# music_box.net
KiCad netlist of a schematic drawn in EAGLE
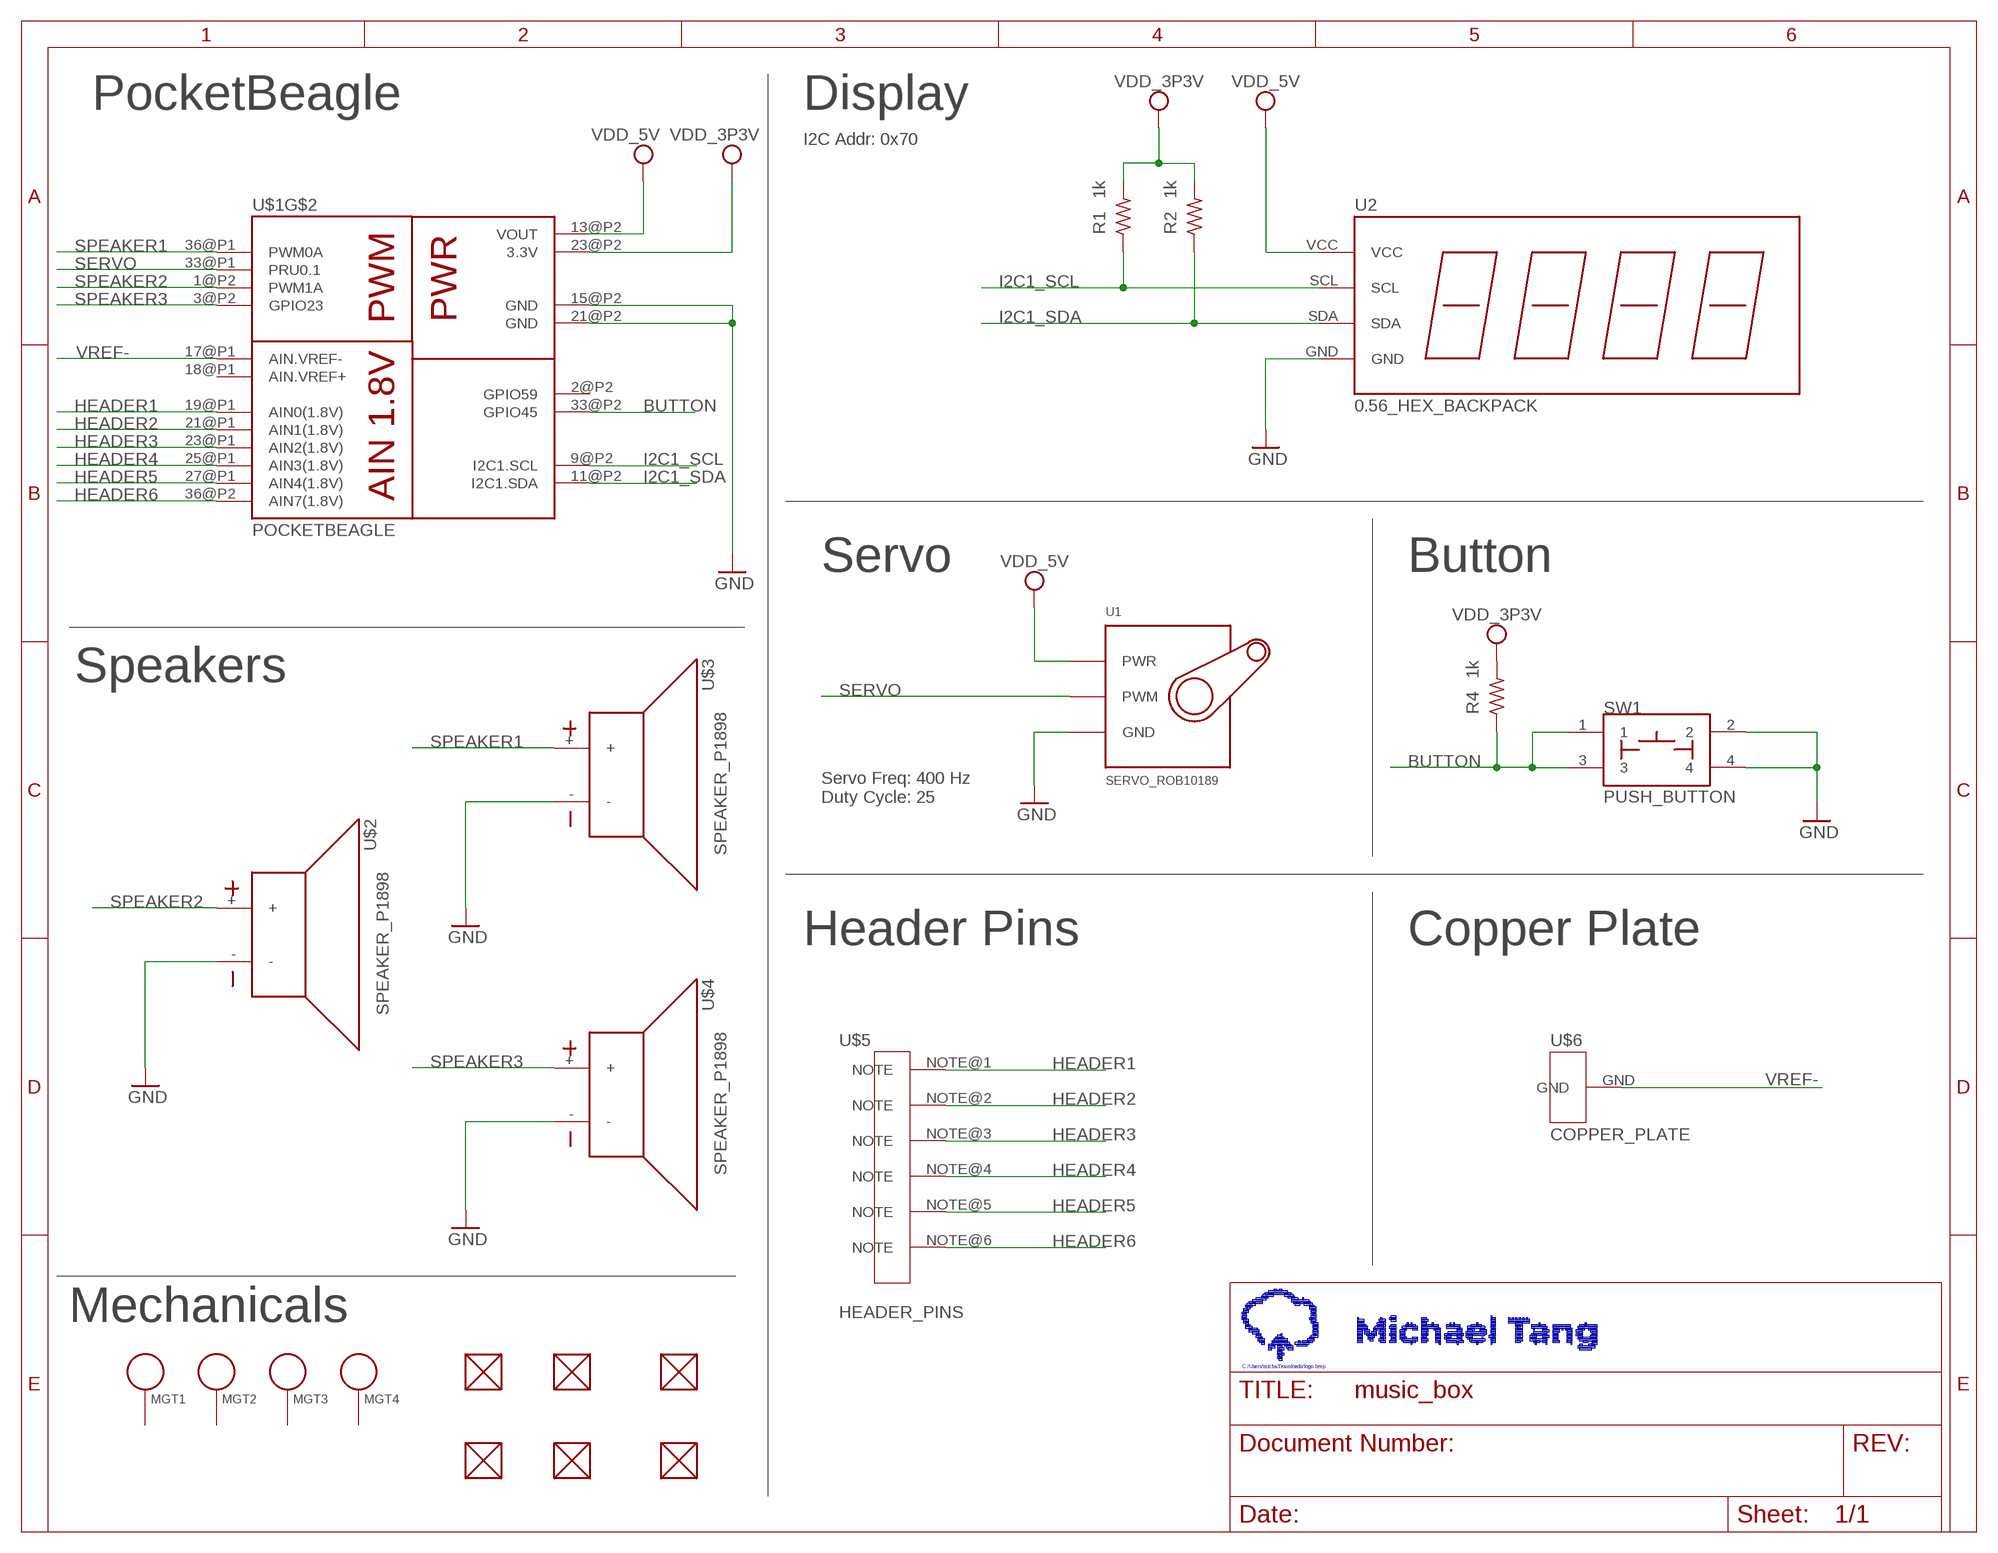
[diagram p0: schematic, sheet 1]

(export (version "E")
  (design (tool "Eeschema 10.0.6"))
  (components
    (comp (ref "FUD1")
      (value "FIDUCIAL")
      (footprint "eagle-import:FIDUCIAL_40MIL")
      (libsource (lib "eagle-import") (part "FIDUCIAL"))
    )
    (comp (ref "FUD2")
      (value "FIDUCIAL")
      (footprint "eagle-import:FIDUCIAL_40MIL")
      (libsource (lib "eagle-import") (part "FIDUCIAL"))
    )
    (comp (ref "FUD3")
      (value "FIDUCIAL")
      (footprint "eagle-import:FIDUCIAL_40MIL")
      (libsource (lib "eagle-import") (part "FIDUCIAL"))
    )
    (comp (ref "FUD4")
      (value "FIDUCIAL")
      (footprint "eagle-import:FIDUCIAL_40MIL")
      (libsource (lib "eagle-import") (part "FIDUCIAL"))
    )
    (comp (ref "FUD5")
      (value "FIDUCIAL")
      (footprint "eagle-import:FIDUCIAL_40MIL")
      (libsource (lib "eagle-import") (part "FIDUCIAL"))
    )
    (comp (ref "FUD6")
      (value "FIDUCIAL")
      (footprint "eagle-import:FIDUCIAL_40MIL")
      (libsource (lib "eagle-import") (part "FIDUCIAL"))
    )
    (comp (ref "MGT1")
      (value "MOUNTING_HOLE")
      (footprint "eagle-import:MOUNTING_HOLE")
      (libsource (lib "eagle-import") (part "MOUNTING_HOLE"))
    )
    (comp (ref "MGT2")
      (value "MOUNTING_HOLE")
      (footprint "eagle-import:MOUNTING_HOLE")
      (libsource (lib "eagle-import") (part "MOUNTING_HOLE"))
    )
    (comp (ref "MGT3")
      (value "MOUNTING_HOLE")
      (footprint "eagle-import:MOUNTING_HOLE")
      (libsource (lib "eagle-import") (part "MOUNTING_HOLE"))
    )
    (comp (ref "MGT4")
      (value "MOUNTING_HOLE")
      (footprint "eagle-import:MOUNTING_HOLE")
      (libsource (lib "eagle-import") (part "MOUNTING_HOLE"))
    )
    (comp (ref "R1")
      (value "1k")
      (footprint "eagle-import:R0603")
      (libsource (lib "eagle-import") (part "R_R0603"))
    )
    (comp (ref "R2")
      (value "1k")
      (footprint "eagle-import:R0603")
      (libsource (lib "eagle-import") (part "R_R0603"))
    )
    (comp (ref "R4")
      (value "1k")
      (footprint "eagle-import:R0603")
      (libsource (lib "eagle-import") (part "R_R0603"))
    )
    (comp (ref "SW1")
      (value "PUSH_BUTTON")
      (footprint "eagle-import:BUTTON_12.5MM")
      (libsource (lib "eagle-import") (part "PUSH_BUTTON"))
    )
    (comp (ref "U$1")
      (value "POCKETBEAGLE")
      (footprint "eagle-import:POCKETBEAGLE")
      (libsource (lib "eagle-import") (part "POCKETBEAGLE"))
    )
    (comp (ref "U$2")
      (value "SPEAKER_P1898")
      (footprint "eagle-import:SPEAKER")
      (libsource (lib "eagle-import") (part "SPEAKER_P1898"))
    )
    (comp (ref "U$3")
      (value "SPEAKER_P1898")
      (footprint "eagle-import:SPEAKER")
      (libsource (lib "eagle-import") (part "SPEAKER_P1898"))
    )
    (comp (ref "U$4")
      (value "SPEAKER_P1898")
      (footprint "eagle-import:SPEAKER")
      (libsource (lib "eagle-import") (part "SPEAKER_P1898"))
    )
    (comp (ref "U$5")
      (value "HEADER_PINS")
      (footprint "eagle-import:HEADER_PINS")
      (libsource (lib "eagle-import") (part "HEADER_PINS"))
    )
    (comp (ref "U$6")
      (value "COPPER_PLATE")
      (footprint "eagle-import:COPPER_PLATE")
      (libsource (lib "eagle-import") (part "COPPER_PLATE"))
    )
    (comp (ref "U1")
      (value "SERVO_ROB10189")
      (footprint "eagle-import:SERVO-X1")
      (libsource (lib "eagle-import") (part "SERVO_ROB10189"))
    )
    (comp (ref "U2")
      (value "0.56_HEX_BACKPACK")
      (footprint "eagle-import:0.56_HEX_BACKPACK")
      (libsource (lib "eagle-import") (part "0.56_HEX_BACKPACK"))
    )
  )
  (nets
    (net (code "1") (name "/BUTTON") (class "Default")
      (node (ref "R4") (pin "1") (pinfunction "1_1") (pintype "passive"))
      (node (ref "SW1") (pin "1") (pinfunction "1_1") (pintype "bidirectional"))
      (node (ref "SW1") (pin "3") (pinfunction "3_3") (pintype "bidirectional"))
      (node (ref "U$1") (pin "33@P2") (pinfunction "GPIO45_33@P2") (pintype "bidirectional"))
    )
    (net (code "2") (name "/HEADER1") (class "Default")
      (node (ref "U$1") (pin "19@P1") (pinfunction "AIN0(1.8V)_19@P1") (pintype "bidirectional"))
      (node (ref "U$5") (pin "NOTE@1") (pinfunction "NOTE_NOTE@1") (pintype "bidirectional"))
    )
    (net (code "3") (name "/HEADER2") (class "Default")
      (node (ref "U$1") (pin "21@P1") (pinfunction "AIN1(1.8V)_21@P1") (pintype "bidirectional"))
      (node (ref "U$5") (pin "NOTE@2") (pinfunction "NOTE_NOTE@2") (pintype "bidirectional"))
    )
    (net (code "4") (name "/HEADER3") (class "Default")
      (node (ref "U$1") (pin "23@P1") (pinfunction "AIN2(1.8V)_23@P1") (pintype "bidirectional"))
      (node (ref "U$5") (pin "NOTE@3") (pinfunction "NOTE_NOTE@3") (pintype "bidirectional"))
    )
    (net (code "5") (name "/HEADER4") (class "Default")
      (node (ref "U$1") (pin "25@P1") (pinfunction "AIN3(1.8V)_25@P1") (pintype "bidirectional"))
      (node (ref "U$5") (pin "NOTE@4") (pinfunction "NOTE_NOTE@4") (pintype "bidirectional"))
    )
    (net (code "6") (name "/HEADER5") (class "Default")
      (node (ref "U$1") (pin "27@P1") (pinfunction "AIN4(1.8V)_27@P1") (pintype "bidirectional"))
      (node (ref "U$5") (pin "NOTE@5") (pinfunction "NOTE_NOTE@5") (pintype "bidirectional"))
    )
    (net (code "7") (name "/HEADER6") (class "Default")
      (node (ref "U$1") (pin "36@P2") (pinfunction "AIN7(1.8V)_36@P2") (pintype "bidirectional"))
      (node (ref "U$5") (pin "NOTE@6") (pinfunction "NOTE_NOTE@6") (pintype "bidirectional"))
    )
    (net (code "8") (name "/I2C1_SCL") (class "Default")
      (node (ref "R1") (pin "1") (pinfunction "1_1") (pintype "passive"))
      (node (ref "U$1") (pin "9@P2") (pinfunction "I2C1.SCL_9@P2") (pintype "bidirectional"))
      (node (ref "U2") (pin "SCL") (pinfunction "SCL_SCL") (pintype "bidirectional"))
    )
    (net (code "9") (name "/I2C1_SDA") (class "Default")
      (node (ref "R2") (pin "1") (pinfunction "1_1") (pintype "passive"))
      (node (ref "U$1") (pin "11@P2") (pinfunction "I2C1.SDA_11@P2") (pintype "bidirectional"))
      (node (ref "U2") (pin "SDA") (pinfunction "SDA_SDA") (pintype "bidirectional"))
    )
    (net (code "10") (name "/SERVO") (class "Default")
      (node (ref "U$1") (pin "33@P1") (pinfunction "PRU0.1_33@P1") (pintype "bidirectional"))
      (node (ref "U1") (pin "SIG") (pinfunction "PWM_SIG") (pintype "bidirectional"))
    )
    (net (code "11") (name "/SPEAKER1") (class "Default")
      (node (ref "U$1") (pin "36@P1") (pinfunction "PWM0A_36@P1") (pintype "bidirectional"))
      (node (ref "U$3") (pin "+") (pinfunction "+_+") (pintype "bidirectional"))
    )
    (net (code "12") (name "/SPEAKER2") (class "Default")
      (node (ref "U$1") (pin "1@P2") (pinfunction "PWM1A_1@P2") (pintype "bidirectional"))
      (node (ref "U$2") (pin "+") (pinfunction "+_+") (pintype "bidirectional"))
    )
    (net (code "13") (name "/SPEAKER3") (class "Default")
      (node (ref "U$1") (pin "3@P2") (pinfunction "GPIO23_3@P2") (pintype "bidirectional"))
      (node (ref "U$4") (pin "+") (pinfunction "+_+") (pintype "bidirectional"))
    )
    (net (code "14") (name "/VREF-") (class "Default")
      (node (ref "U$1") (pin "17@P1") (pinfunction "AIN.VREF-_17@P1") (pintype "bidirectional"))
      (node (ref "U$6") (pin "GND") (pinfunction "GND_GND") (pintype "bidirectional"))
    )
    (net (code "15") (name "GND") (class "Default")
      (node (ref "SW1") (pin "2") (pinfunction "2_2") (pintype "bidirectional"))
      (node (ref "SW1") (pin "4") (pinfunction "4_4") (pintype "bidirectional"))
      (node (ref "U$1") (pin "15@P2") (pinfunction "GND_15@P2") (pintype "bidirectional"))
      (node (ref "U$1") (pin "21@P2") (pinfunction "GND_21@P2") (pintype "bidirectional"))
      (node (ref "U$2") (pin "-") (pinfunction "-_-") (pintype "bidirectional"))
      (node (ref "U$3") (pin "-") (pinfunction "-_-") (pintype "bidirectional"))
      (node (ref "U$4") (pin "-") (pinfunction "-_-") (pintype "bidirectional"))
      (node (ref "U1") (pin "GND") (pinfunction "GND_GND") (pintype "bidirectional"))
      (node (ref "U2") (pin "GND") (pinfunction "GND_GND") (pintype "bidirectional"))
    )
    (net (code "16") (name "VDD_3P3V") (class "Default")
      (node (ref "R1") (pin "2") (pinfunction "2_2") (pintype "passive"))
      (node (ref "R2") (pin "2") (pinfunction "2_2") (pintype "passive"))
      (node (ref "R4") (pin "2") (pinfunction "2_2") (pintype "passive"))
      (node (ref "U$1") (pin "23@P2") (pinfunction "3.3V_23@P2") (pintype "bidirectional"))
    )
    (net (code "17") (name "VDD_5V") (class "Default")
      (node (ref "U$1") (pin "13@P2") (pinfunction "VOUT_13@P2") (pintype "bidirectional"))
      (node (ref "U1") (pin "PWR") (pinfunction "PWR_PWR") (pintype "bidirectional"))
      (node (ref "U2") (pin "VCC") (pinfunction "VCC_VCC") (pintype "power_in"))
    )
    (net (code "18") (name "unconnected-(FUD1-PadP$1)") (class "Default")
      (node (ref "FUD1") (pin "P$1") (pinfunction "P$1_P$1") (pintype "no_connect"))
    )
    (net (code "19") (name "unconnected-(FUD2-PadP$1)") (class "Default")
      (node (ref "FUD2") (pin "P$1") (pinfunction "P$1_P$1") (pintype "no_connect"))
    )
    (net (code "20") (name "unconnected-(FUD3-PadP$1)") (class "Default")
      (node (ref "FUD3") (pin "P$1") (pinfunction "P$1_P$1") (pintype "no_connect"))
    )
    (net (code "21") (name "unconnected-(FUD4-PadP$1)") (class "Default")
      (node (ref "FUD4") (pin "P$1") (pinfunction "P$1_P$1") (pintype "no_connect"))
    )
    (net (code "22") (name "unconnected-(FUD5-PadP$1)") (class "Default")
      (node (ref "FUD5") (pin "P$1") (pinfunction "P$1_P$1") (pintype "no_connect"))
    )
    (net (code "23") (name "unconnected-(FUD6-PadP$1)") (class "Default")
      (node (ref "FUD6") (pin "P$1") (pinfunction "P$1_P$1") (pintype "no_connect"))
    )
    (net (code "24") (name "unconnected-(MGT1-PadP$1)") (class "Default")
      (node (ref "MGT1") (pin "P$1") (pinfunction "P$1_P$1") (pintype "bidirectional"))
    )
    (net (code "25") (name "unconnected-(MGT2-PadP$1)") (class "Default")
      (node (ref "MGT2") (pin "P$1") (pinfunction "P$1_P$1") (pintype "bidirectional"))
    )
    (net (code "26") (name "unconnected-(MGT3-PadP$1)") (class "Default")
      (node (ref "MGT3") (pin "P$1") (pinfunction "P$1_P$1") (pintype "bidirectional"))
    )
    (net (code "27") (name "unconnected-(MGT4-PadP$1)") (class "Default")
      (node (ref "MGT4") (pin "P$1") (pinfunction "P$1_P$1") (pintype "bidirectional"))
    )
    (net (code "28") (name "unconnected-(U$1B-AIN.VREF+-Pad18@P1)") (class "Default")
      (node (ref "U$1") (pin "18@P1") (pinfunction "AIN.VREF+_18@P1") (pintype "bidirectional"))
    )
    (net (code "29") (name "unconnected-(U$1B-GPIO59-Pad2@P2)") (class "Default")
      (node (ref "U$1") (pin "2@P2") (pinfunction "GPIO59_2@P2") (pintype "bidirectional"))
    )
  )
)
